# SubBus11.net
KiCad netlist of a schematic drawn in Altium Designer
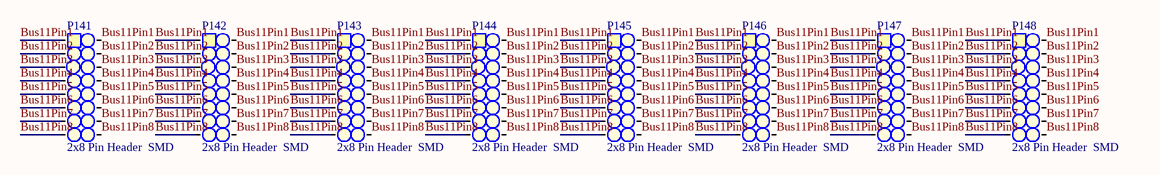
[diagram p0: SubBus11.SchDoc]

(export (version "E")
  (design (tool "Eeschema 10.0.6"))
  (components
    (comp (ref "P141")
      (value "2x8 Pin Header  SMD")
      (footprint "2X8_SMD_PH_2.54")
      (description "2.54mm, SMD")
      (libsource (lib "jclib") (part "2x8 Pin Header  SMD"))
    )
    (comp (ref "P142")
      (value "2x8 Pin Header  SMD")
      (footprint "2X8_SMD_PH_2.54")
      (description "2.54mm, SMD")
      (libsource (lib "jclib") (part "2x8 Pin Header  SMD"))
    )
    (comp (ref "P143")
      (value "2x8 Pin Header  SMD")
      (footprint "2X8_SMD_PH_2.54")
      (description "2.54mm, SMD")
      (libsource (lib "jclib") (part "2x8 Pin Header  SMD"))
    )
    (comp (ref "P144")
      (value "2x8 Pin Header  SMD")
      (footprint "2X8_SMD_PH_2.54")
      (description "2.54mm, SMD")
      (libsource (lib "jclib") (part "2x8 Pin Header  SMD"))
    )
    (comp (ref "P145")
      (value "2x8 Pin Header  SMD")
      (footprint "2X8_SMD_PH_2.54")
      (description "2.54mm, SMD")
      (libsource (lib "jclib") (part "2x8 Pin Header  SMD"))
    )
    (comp (ref "P146")
      (value "2x8 Pin Header  SMD")
      (footprint "2X8_SMD_PH_2.54")
      (description "2.54mm, SMD")
      (libsource (lib "jclib") (part "2x8 Pin Header  SMD"))
    )
    (comp (ref "P147")
      (value "2x8 Pin Header  SMD")
      (footprint "2X8_SMD_PH_2.54")
      (description "2.54mm, SMD")
      (libsource (lib "jclib") (part "2x8 Pin Header  SMD"))
    )
    (comp (ref "P148")
      (value "2x8 Pin Header  SMD")
      (footprint "2X8_SMD_PH_2.54")
      (description "2.54mm, SMD")
      (libsource (lib "jclib") (part "2x8 Pin Header  SMD"))
    )
  )
  (nets
    (net (code "1") (name "/Bus11Pin1") (class "Default")
      (node (ref "P141") (pin "1") (pinfunction "1_1") (pintype "passive"))
      (node (ref "P141") (pin "16") (pinfunction "16_16") (pintype "passive"))
      (node (ref "P142") (pin "1") (pinfunction "1_1") (pintype "passive"))
      (node (ref "P142") (pin "16") (pinfunction "16_16") (pintype "passive"))
      (node (ref "P143") (pin "1") (pinfunction "1_1") (pintype "passive"))
      (node (ref "P143") (pin "16") (pinfunction "16_16") (pintype "passive"))
      (node (ref "P144") (pin "1") (pinfunction "1_1") (pintype "passive"))
      (node (ref "P144") (pin "16") (pinfunction "16_16") (pintype "passive"))
      (node (ref "P145") (pin "1") (pinfunction "1_1") (pintype "passive"))
      (node (ref "P145") (pin "16") (pinfunction "16_16") (pintype "passive"))
      (node (ref "P146") (pin "1") (pinfunction "1_1") (pintype "passive"))
      (node (ref "P146") (pin "16") (pinfunction "16_16") (pintype "passive"))
      (node (ref "P147") (pin "1") (pinfunction "1_1") (pintype "passive"))
      (node (ref "P147") (pin "16") (pinfunction "16_16") (pintype "passive"))
      (node (ref "P148") (pin "1") (pinfunction "1_1") (pintype "passive"))
      (node (ref "P148") (pin "16") (pinfunction "16_16") (pintype "passive"))
    )
    (net (code "2") (name "/Bus11Pin2") (class "Default")
      (node (ref "P141") (pin "15") (pinfunction "15_15") (pintype "passive"))
      (node (ref "P141") (pin "2") (pinfunction "2_2") (pintype "passive"))
      (node (ref "P142") (pin "15") (pinfunction "15_15") (pintype "passive"))
      (node (ref "P142") (pin "2") (pinfunction "2_2") (pintype "passive"))
      (node (ref "P143") (pin "15") (pinfunction "15_15") (pintype "passive"))
      (node (ref "P143") (pin "2") (pinfunction "2_2") (pintype "passive"))
      (node (ref "P144") (pin "15") (pinfunction "15_15") (pintype "passive"))
      (node (ref "P144") (pin "2") (pinfunction "2_2") (pintype "passive"))
      (node (ref "P145") (pin "15") (pinfunction "15_15") (pintype "passive"))
      (node (ref "P145") (pin "2") (pinfunction "2_2") (pintype "passive"))
      (node (ref "P146") (pin "15") (pinfunction "15_15") (pintype "passive"))
      (node (ref "P146") (pin "2") (pinfunction "2_2") (pintype "passive"))
      (node (ref "P147") (pin "15") (pinfunction "15_15") (pintype "passive"))
      (node (ref "P147") (pin "2") (pinfunction "2_2") (pintype "passive"))
      (node (ref "P148") (pin "15") (pinfunction "15_15") (pintype "passive"))
      (node (ref "P148") (pin "2") (pinfunction "2_2") (pintype "passive"))
    )
    (net (code "3") (name "/Bus11Pin3") (class "Default")
      (node (ref "P141") (pin "14") (pinfunction "14_14") (pintype "passive"))
      (node (ref "P141") (pin "3") (pinfunction "3_3") (pintype "passive"))
      (node (ref "P142") (pin "14") (pinfunction "14_14") (pintype "passive"))
      (node (ref "P142") (pin "3") (pinfunction "3_3") (pintype "passive"))
      (node (ref "P143") (pin "14") (pinfunction "14_14") (pintype "passive"))
      (node (ref "P143") (pin "3") (pinfunction "3_3") (pintype "passive"))
      (node (ref "P144") (pin "14") (pinfunction "14_14") (pintype "passive"))
      (node (ref "P144") (pin "3") (pinfunction "3_3") (pintype "passive"))
      (node (ref "P145") (pin "14") (pinfunction "14_14") (pintype "passive"))
      (node (ref "P145") (pin "3") (pinfunction "3_3") (pintype "passive"))
      (node (ref "P146") (pin "14") (pinfunction "14_14") (pintype "passive"))
      (node (ref "P146") (pin "3") (pinfunction "3_3") (pintype "passive"))
      (node (ref "P147") (pin "14") (pinfunction "14_14") (pintype "passive"))
      (node (ref "P147") (pin "3") (pinfunction "3_3") (pintype "passive"))
      (node (ref "P148") (pin "14") (pinfunction "14_14") (pintype "passive"))
      (node (ref "P148") (pin "3") (pinfunction "3_3") (pintype "passive"))
    )
    (net (code "4") (name "/Bus11Pin4") (class "Default")
      (node (ref "P141") (pin "13") (pinfunction "13_13") (pintype "passive"))
      (node (ref "P141") (pin "4") (pinfunction "4_4") (pintype "passive"))
      (node (ref "P142") (pin "13") (pinfunction "13_13") (pintype "passive"))
      (node (ref "P142") (pin "4") (pinfunction "4_4") (pintype "passive"))
      (node (ref "P143") (pin "13") (pinfunction "13_13") (pintype "passive"))
      (node (ref "P143") (pin "4") (pinfunction "4_4") (pintype "passive"))
      (node (ref "P144") (pin "13") (pinfunction "13_13") (pintype "passive"))
      (node (ref "P144") (pin "4") (pinfunction "4_4") (pintype "passive"))
      (node (ref "P145") (pin "13") (pinfunction "13_13") (pintype "passive"))
      (node (ref "P145") (pin "4") (pinfunction "4_4") (pintype "passive"))
      (node (ref "P146") (pin "13") (pinfunction "13_13") (pintype "passive"))
      (node (ref "P146") (pin "4") (pinfunction "4_4") (pintype "passive"))
      (node (ref "P147") (pin "13") (pinfunction "13_13") (pintype "passive"))
      (node (ref "P147") (pin "4") (pinfunction "4_4") (pintype "passive"))
      (node (ref "P148") (pin "13") (pinfunction "13_13") (pintype "passive"))
      (node (ref "P148") (pin "4") (pinfunction "4_4") (pintype "passive"))
    )
    (net (code "5") (name "/Bus11Pin5") (class "Default")
      (node (ref "P141") (pin "12") (pinfunction "12_12") (pintype "passive"))
      (node (ref "P141") (pin "5") (pinfunction "5_5") (pintype "passive"))
      (node (ref "P142") (pin "12") (pinfunction "12_12") (pintype "passive"))
      (node (ref "P142") (pin "5") (pinfunction "5_5") (pintype "passive"))
      (node (ref "P143") (pin "12") (pinfunction "12_12") (pintype "passive"))
      (node (ref "P143") (pin "5") (pinfunction "5_5") (pintype "passive"))
      (node (ref "P144") (pin "12") (pinfunction "12_12") (pintype "passive"))
      (node (ref "P144") (pin "5") (pinfunction "5_5") (pintype "passive"))
      (node (ref "P145") (pin "12") (pinfunction "12_12") (pintype "passive"))
      (node (ref "P145") (pin "5") (pinfunction "5_5") (pintype "passive"))
      (node (ref "P146") (pin "12") (pinfunction "12_12") (pintype "passive"))
      (node (ref "P146") (pin "5") (pinfunction "5_5") (pintype "passive"))
      (node (ref "P147") (pin "12") (pinfunction "12_12") (pintype "passive"))
      (node (ref "P147") (pin "5") (pinfunction "5_5") (pintype "passive"))
      (node (ref "P148") (pin "12") (pinfunction "12_12") (pintype "passive"))
      (node (ref "P148") (pin "5") (pinfunction "5_5") (pintype "passive"))
    )
    (net (code "6") (name "/Bus11Pin6") (class "Default")
      (node (ref "P141") (pin "11") (pinfunction "11_11") (pintype "passive"))
      (node (ref "P141") (pin "6") (pinfunction "6_6") (pintype "passive"))
      (node (ref "P142") (pin "11") (pinfunction "11_11") (pintype "passive"))
      (node (ref "P142") (pin "6") (pinfunction "6_6") (pintype "passive"))
      (node (ref "P143") (pin "11") (pinfunction "11_11") (pintype "passive"))
      (node (ref "P143") (pin "6") (pinfunction "6_6") (pintype "passive"))
      (node (ref "P144") (pin "11") (pinfunction "11_11") (pintype "passive"))
      (node (ref "P144") (pin "6") (pinfunction "6_6") (pintype "passive"))
      (node (ref "P145") (pin "11") (pinfunction "11_11") (pintype "passive"))
      (node (ref "P145") (pin "6") (pinfunction "6_6") (pintype "passive"))
      (node (ref "P146") (pin "11") (pinfunction "11_11") (pintype "passive"))
      (node (ref "P146") (pin "6") (pinfunction "6_6") (pintype "passive"))
      (node (ref "P147") (pin "11") (pinfunction "11_11") (pintype "passive"))
      (node (ref "P147") (pin "6") (pinfunction "6_6") (pintype "passive"))
      (node (ref "P148") (pin "11") (pinfunction "11_11") (pintype "passive"))
      (node (ref "P148") (pin "6") (pinfunction "6_6") (pintype "passive"))
    )
    (net (code "7") (name "/Bus11Pin7") (class "Default")
      (node (ref "P141") (pin "10") (pinfunction "10_10") (pintype "passive"))
      (node (ref "P141") (pin "7") (pinfunction "7_7") (pintype "passive"))
      (node (ref "P142") (pin "10") (pinfunction "10_10") (pintype "passive"))
      (node (ref "P142") (pin "7") (pinfunction "7_7") (pintype "passive"))
      (node (ref "P143") (pin "10") (pinfunction "10_10") (pintype "passive"))
      (node (ref "P143") (pin "7") (pinfunction "7_7") (pintype "passive"))
      (node (ref "P144") (pin "10") (pinfunction "10_10") (pintype "passive"))
      (node (ref "P144") (pin "7") (pinfunction "7_7") (pintype "passive"))
      (node (ref "P145") (pin "10") (pinfunction "10_10") (pintype "passive"))
      (node (ref "P145") (pin "7") (pinfunction "7_7") (pintype "passive"))
      (node (ref "P146") (pin "10") (pinfunction "10_10") (pintype "passive"))
      (node (ref "P146") (pin "7") (pinfunction "7_7") (pintype "passive"))
      (node (ref "P147") (pin "10") (pinfunction "10_10") (pintype "passive"))
      (node (ref "P147") (pin "7") (pinfunction "7_7") (pintype "passive"))
      (node (ref "P148") (pin "10") (pinfunction "10_10") (pintype "passive"))
      (node (ref "P148") (pin "7") (pinfunction "7_7") (pintype "passive"))
    )
    (net (code "8") (name "/Bus11Pin8") (class "Default")
      (node (ref "P141") (pin "8") (pinfunction "8_8") (pintype "passive"))
      (node (ref "P141") (pin "9") (pinfunction "9_9") (pintype "passive"))
      (node (ref "P142") (pin "8") (pinfunction "8_8") (pintype "passive"))
      (node (ref "P142") (pin "9") (pinfunction "9_9") (pintype "passive"))
      (node (ref "P143") (pin "8") (pinfunction "8_8") (pintype "passive"))
      (node (ref "P143") (pin "9") (pinfunction "9_9") (pintype "passive"))
      (node (ref "P144") (pin "8") (pinfunction "8_8") (pintype "passive"))
      (node (ref "P144") (pin "9") (pinfunction "9_9") (pintype "passive"))
      (node (ref "P145") (pin "8") (pinfunction "8_8") (pintype "passive"))
      (node (ref "P145") (pin "9") (pinfunction "9_9") (pintype "passive"))
      (node (ref "P146") (pin "8") (pinfunction "8_8") (pintype "passive"))
      (node (ref "P146") (pin "9") (pinfunction "9_9") (pintype "passive"))
      (node (ref "P147") (pin "8") (pinfunction "8_8") (pintype "passive"))
      (node (ref "P147") (pin "9") (pinfunction "9_9") (pintype "passive"))
      (node (ref "P148") (pin "8") (pinfunction "8_8") (pintype "passive"))
      (node (ref "P148") (pin "9") (pinfunction "9_9") (pintype "passive"))
    )
  )
)
